# m1k-scope-probe.net
KiCad netlist of a schematic drawn in EAGLE
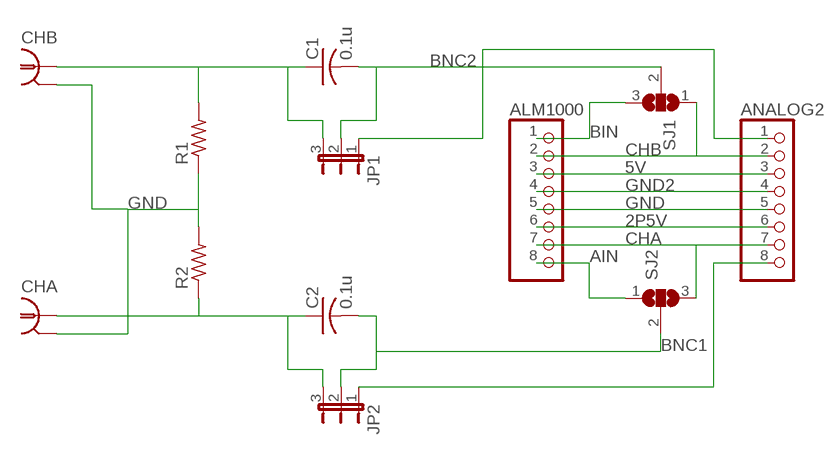
[diagram p0: schematic, sheet 1]

(export (version "E")
  (design (tool "Eeschema 10.0.6"))
  (components
    (comp (ref "ALM1000")
      (value "PINHD-1X8")
      (footprint "eagle-import:1X08")
      (libsource (lib "eagle-import") (part "PINHD-1X8"))
    )
    (comp (ref "ANALOG2")
      (value "PINHD-1X8")
      (footprint "eagle-import:1X08")
      (libsource (lib "eagle-import") (part "PINHD-1X8"))
    )
    (comp (ref "C1")
      (value "0.1u")
      (footprint "eagle-import:C050-024X044")
      (libsource (lib "eagle-import") (part "C-US050-024X044"))
    )
    (comp (ref "C2")
      (value "0.1u")
      (footprint "eagle-import:C050-024X044")
      (libsource (lib "eagle-import") (part "C-US050-024X044"))
    )
    (comp (ref "CHA")
      (value "227161-8")
      (footprint "eagle-import:AMP_227161")
      (libsource (lib "eagle-import") (part "?227161-8"))
    )
    (comp (ref "CHB")
      (value "227161-8")
      (footprint "eagle-import:AMP_227161")
      (libsource (lib "eagle-import") (part "?227161-8"))
    )
    (comp (ref "JP1")
      (value "JP2E")
      (footprint "eagle-import:JP2")
      (libsource (lib "eagle-import") (part "JP2E"))
    )
    (comp (ref "JP2")
      (value "JP2E")
      (footprint "eagle-import:JP2")
      (libsource (lib "eagle-import") (part "JP2E"))
    )
    (comp (ref "R1")
      (value "R-US_0204/7")
      (footprint "eagle-import:0204_7")
      (libsource (lib "eagle-import") (part "R-US_0204/7"))
    )
    (comp (ref "R2")
      (value "R-US_0204/7")
      (footprint "eagle-import:0204_7")
      (libsource (lib "eagle-import") (part "R-US_0204/7"))
    )
    (comp (ref "SJ1")
      (value "SJ2W")
      (footprint "eagle-import:SJ_2")
      (libsource (lib "eagle-import") (part "SJ2W"))
    )
    (comp (ref "SJ2")
      (value "SJ2W")
      (footprint "eagle-import:SJ_2")
      (libsource (lib "eagle-import") (part "SJ2W"))
    )
  )
  (nets
    (net (code "1") (name "/2P5V") (class "Default")
      (node (ref "ALM1000") (pin "6") (pinfunction "6_6") (pintype "passive"))
      (node (ref "ANALOG2") (pin "6") (pinfunction "6_6") (pintype "passive"))
    )
    (net (code "2") (name "/5V") (class "Default")
      (node (ref "ALM1000") (pin "3") (pinfunction "3_3") (pintype "passive"))
      (node (ref "ANALOG2") (pin "3") (pinfunction "3_3") (pintype "passive"))
    )
    (net (code "3") (name "/AIN") (class "Default")
      (node (ref "ALM1000") (pin "8") (pinfunction "8_8") (pintype "passive"))
      (node (ref "SJ2") (pin "1") (pinfunction "1_1") (pintype "passive"))
    )
    (net (code "4") (name "/BIN") (class "Default")
      (node (ref "ALM1000") (pin "1") (pinfunction "1_1") (pintype "passive"))
      (node (ref "SJ1") (pin "3") (pinfunction "3_3") (pintype "passive"))
    )
    (net (code "5") (name "/BNC1") (class "Default")
      (node (ref "C2") (pin "2") (pinfunction "2_2") (pintype "passive"))
      (node (ref "JP2") (pin "2") (pinfunction "2_2") (pintype "passive"))
      (node (ref "SJ2") (pin "2") (pinfunction "2_2") (pintype "passive"))
    )
    (net (code "6") (name "/BNC2") (class "Default")
      (node (ref "C1") (pin "2") (pinfunction "2_2") (pintype "passive"))
      (node (ref "JP1") (pin "2") (pinfunction "2_2") (pintype "passive"))
      (node (ref "SJ1") (pin "2") (pinfunction "2_2") (pintype "passive"))
    )
    (net (code "7") (name "/CHA") (class "Default")
      (node (ref "ALM1000") (pin "7") (pinfunction "7_7") (pintype "passive"))
      (node (ref "ANALOG2") (pin "7") (pinfunction "7_7") (pintype "passive"))
      (node (ref "SJ2") (pin "3") (pinfunction "3_3") (pintype "passive"))
    )
    (net (code "8") (name "/CHB") (class "Default")
      (node (ref "ALM1000") (pin "2") (pinfunction "2_2") (pintype "passive"))
      (node (ref "ANALOG2") (pin "2") (pinfunction "2_2") (pintype "passive"))
      (node (ref "SJ1") (pin "1") (pinfunction "1_1") (pintype "passive"))
    )
    (net (code "9") (name "/GND") (class "Default")
      (node (ref "ALM1000") (pin "5") (pinfunction "5_5") (pintype "passive"))
      (node (ref "ANALOG2") (pin "5") (pinfunction "5_5") (pintype "passive"))
      (node (ref "CHA") (pin "2") (pinfunction "GND_2") (pintype "power_in"))
      (node (ref "CHB") (pin "2") (pinfunction "GND_2") (pintype "power_in"))
      (node (ref "R1") (pin "1") (pinfunction "1_1") (pintype "passive"))
      (node (ref "R2") (pin "2") (pinfunction "2_2") (pintype "passive"))
    )
    (net (code "10") (name "/GND2") (class "Default")
      (node (ref "ALM1000") (pin "4") (pinfunction "4_4") (pintype "passive"))
      (node (ref "ANALOG2") (pin "4") (pinfunction "4_4") (pintype "passive"))
    )
    (net (code "11") (name "Net-(ANALOG2-Pad1)") (class "Default")
      (node (ref "ANALOG2") (pin "1") (pinfunction "1_1") (pintype "passive"))
      (node (ref "JP1") (pin "1") (pinfunction "1_1") (pintype "passive"))
    )
    (net (code "12") (name "Net-(ANALOG2-Pad8)") (class "Default")
      (node (ref "ANALOG2") (pin "8") (pinfunction "8_8") (pintype "passive"))
      (node (ref "JP2") (pin "1") (pinfunction "1_1") (pintype "passive"))
    )
    (net (code "13") (name "Net-(C1-Pad1)") (class "Default")
      (node (ref "C1") (pin "1") (pinfunction "1_1") (pintype "passive"))
      (node (ref "CHB") (pin "1") (pinfunction "1_1") (pintype "passive"))
      (node (ref "JP1") (pin "3") (pinfunction "3_3") (pintype "passive"))
      (node (ref "R1") (pin "2") (pinfunction "2_2") (pintype "passive"))
    )
    (net (code "14") (name "Net-(C2-Pad1)") (class "Default")
      (node (ref "C2") (pin "1") (pinfunction "1_1") (pintype "passive"))
      (node (ref "CHA") (pin "1") (pinfunction "1_1") (pintype "passive"))
      (node (ref "JP2") (pin "3") (pinfunction "3_3") (pintype "passive"))
      (node (ref "R2") (pin "1") (pinfunction "1_1") (pintype "passive"))
    )
  )
)
